# AAA-SeSi_-SCH.net
KiCad netlist of a schematic drawn in EasyEDA
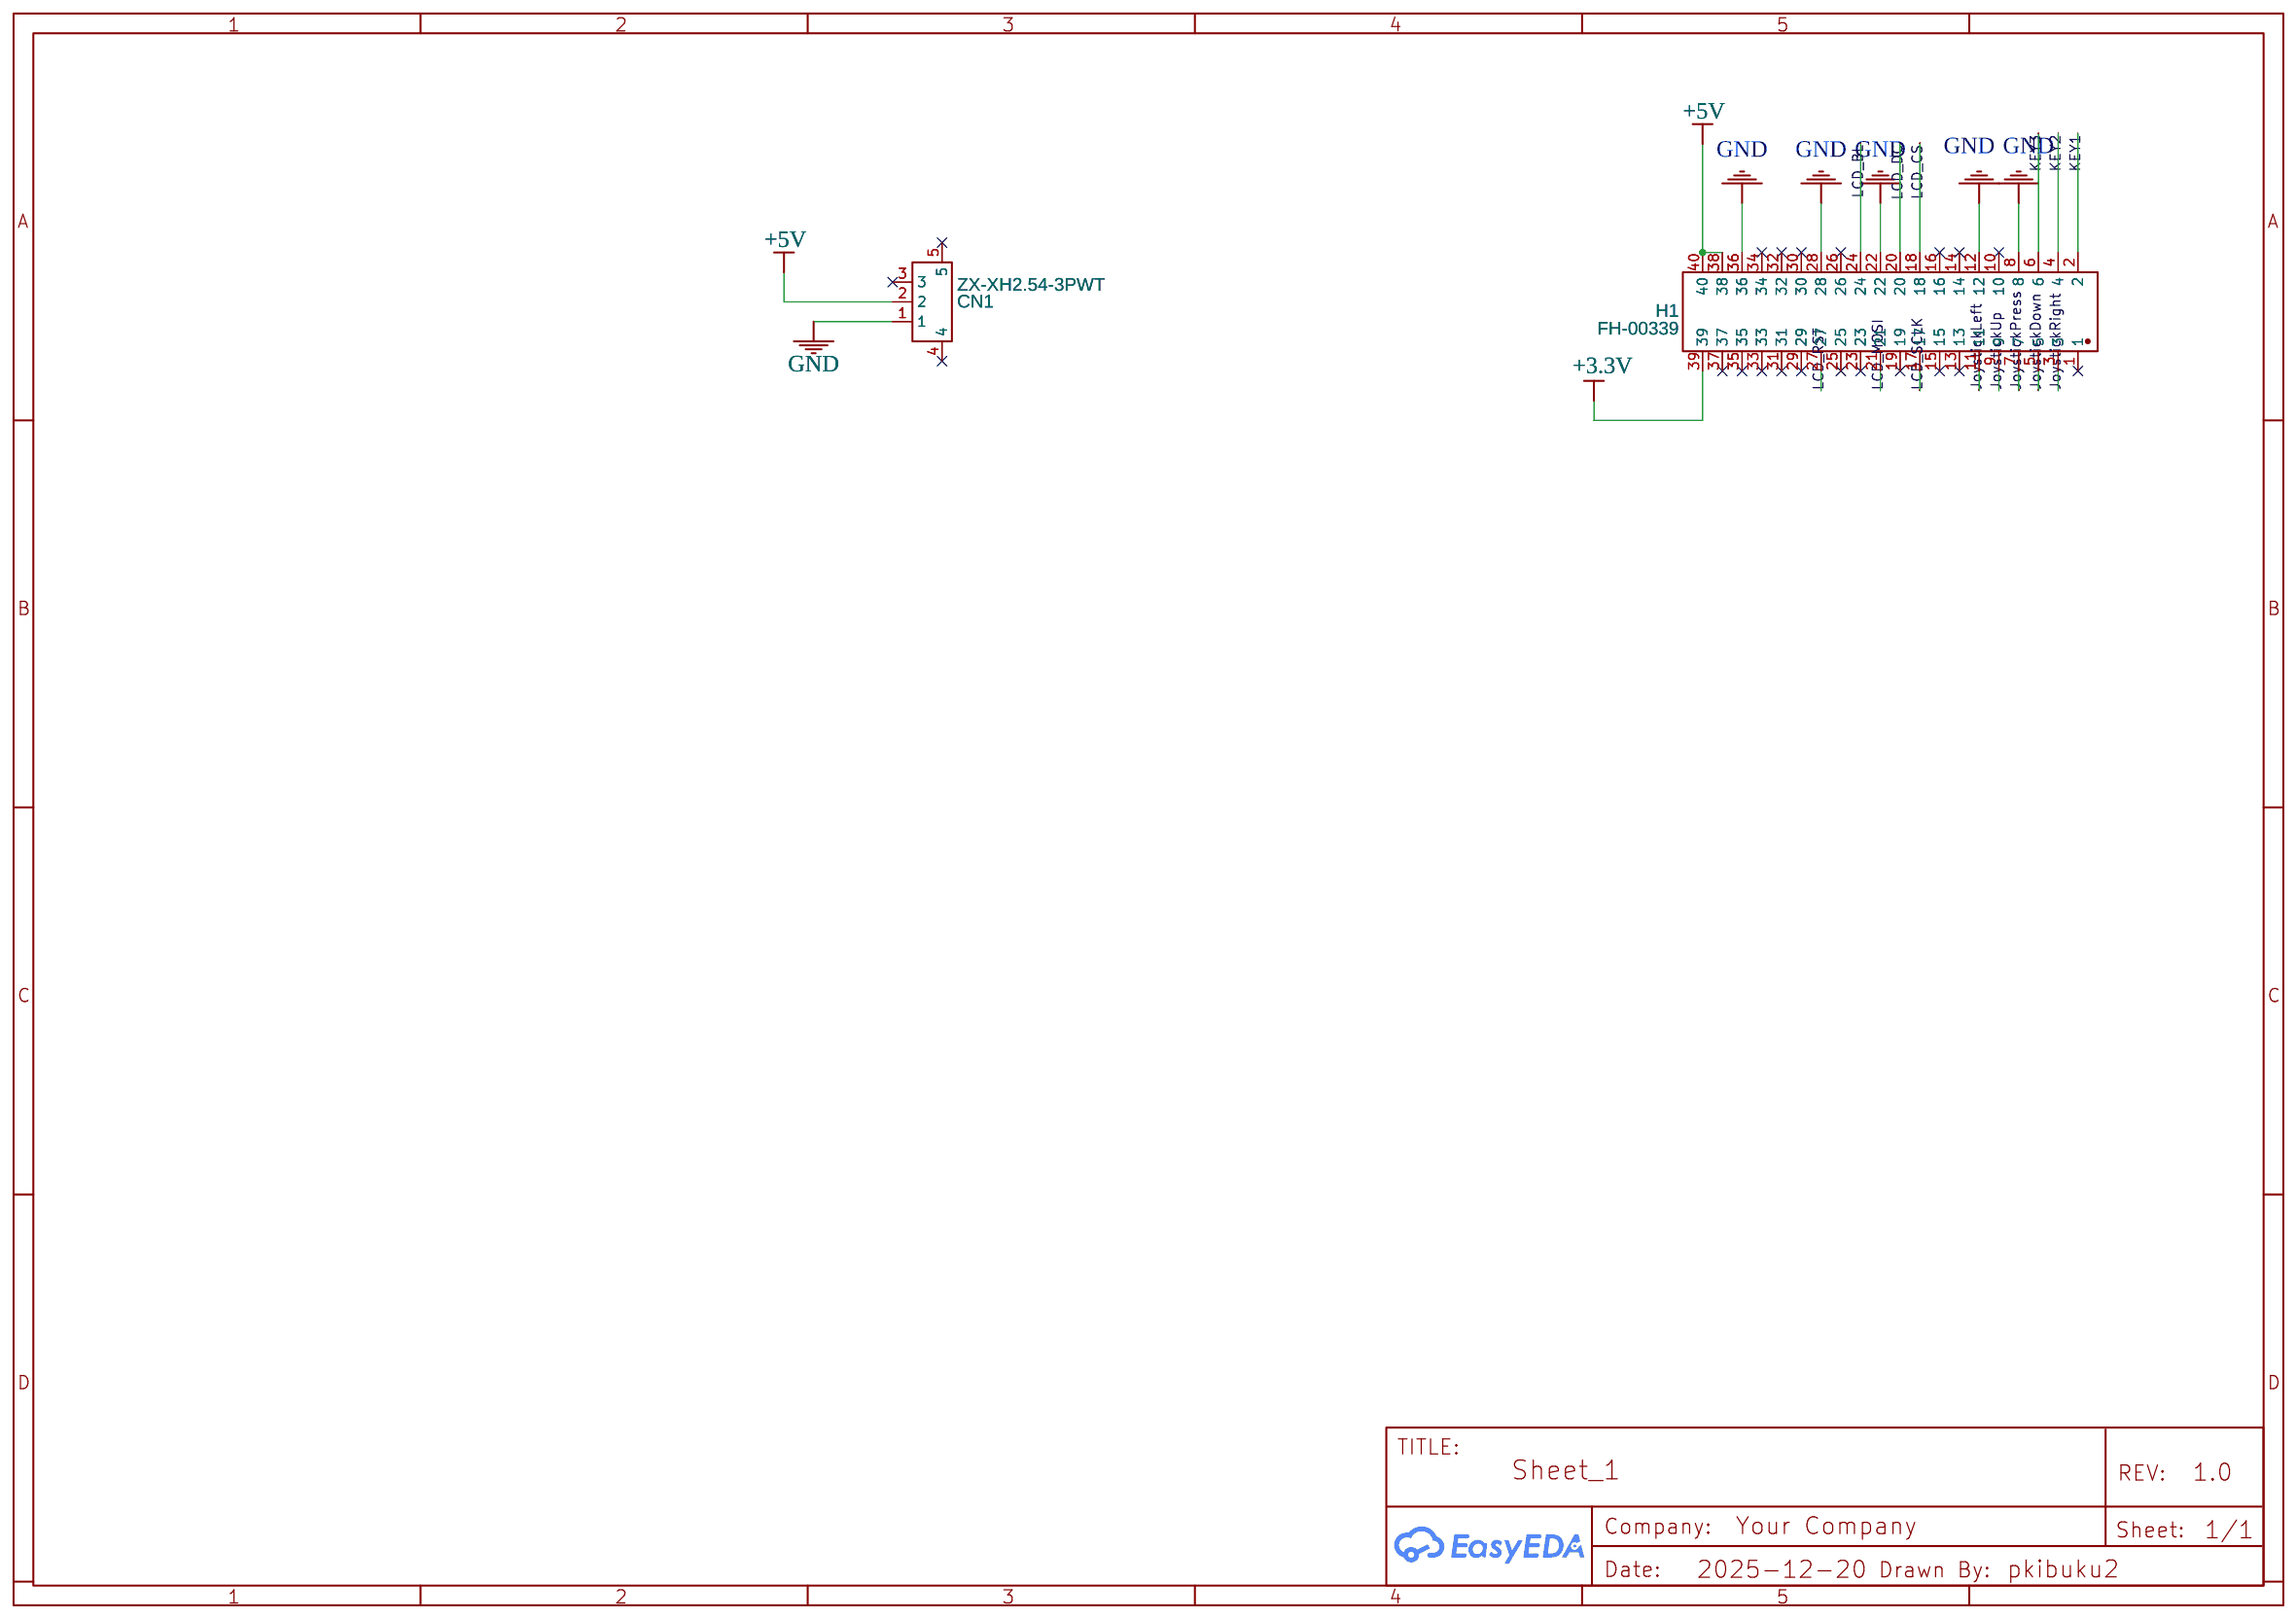
[diagram p0: Sheet_1]
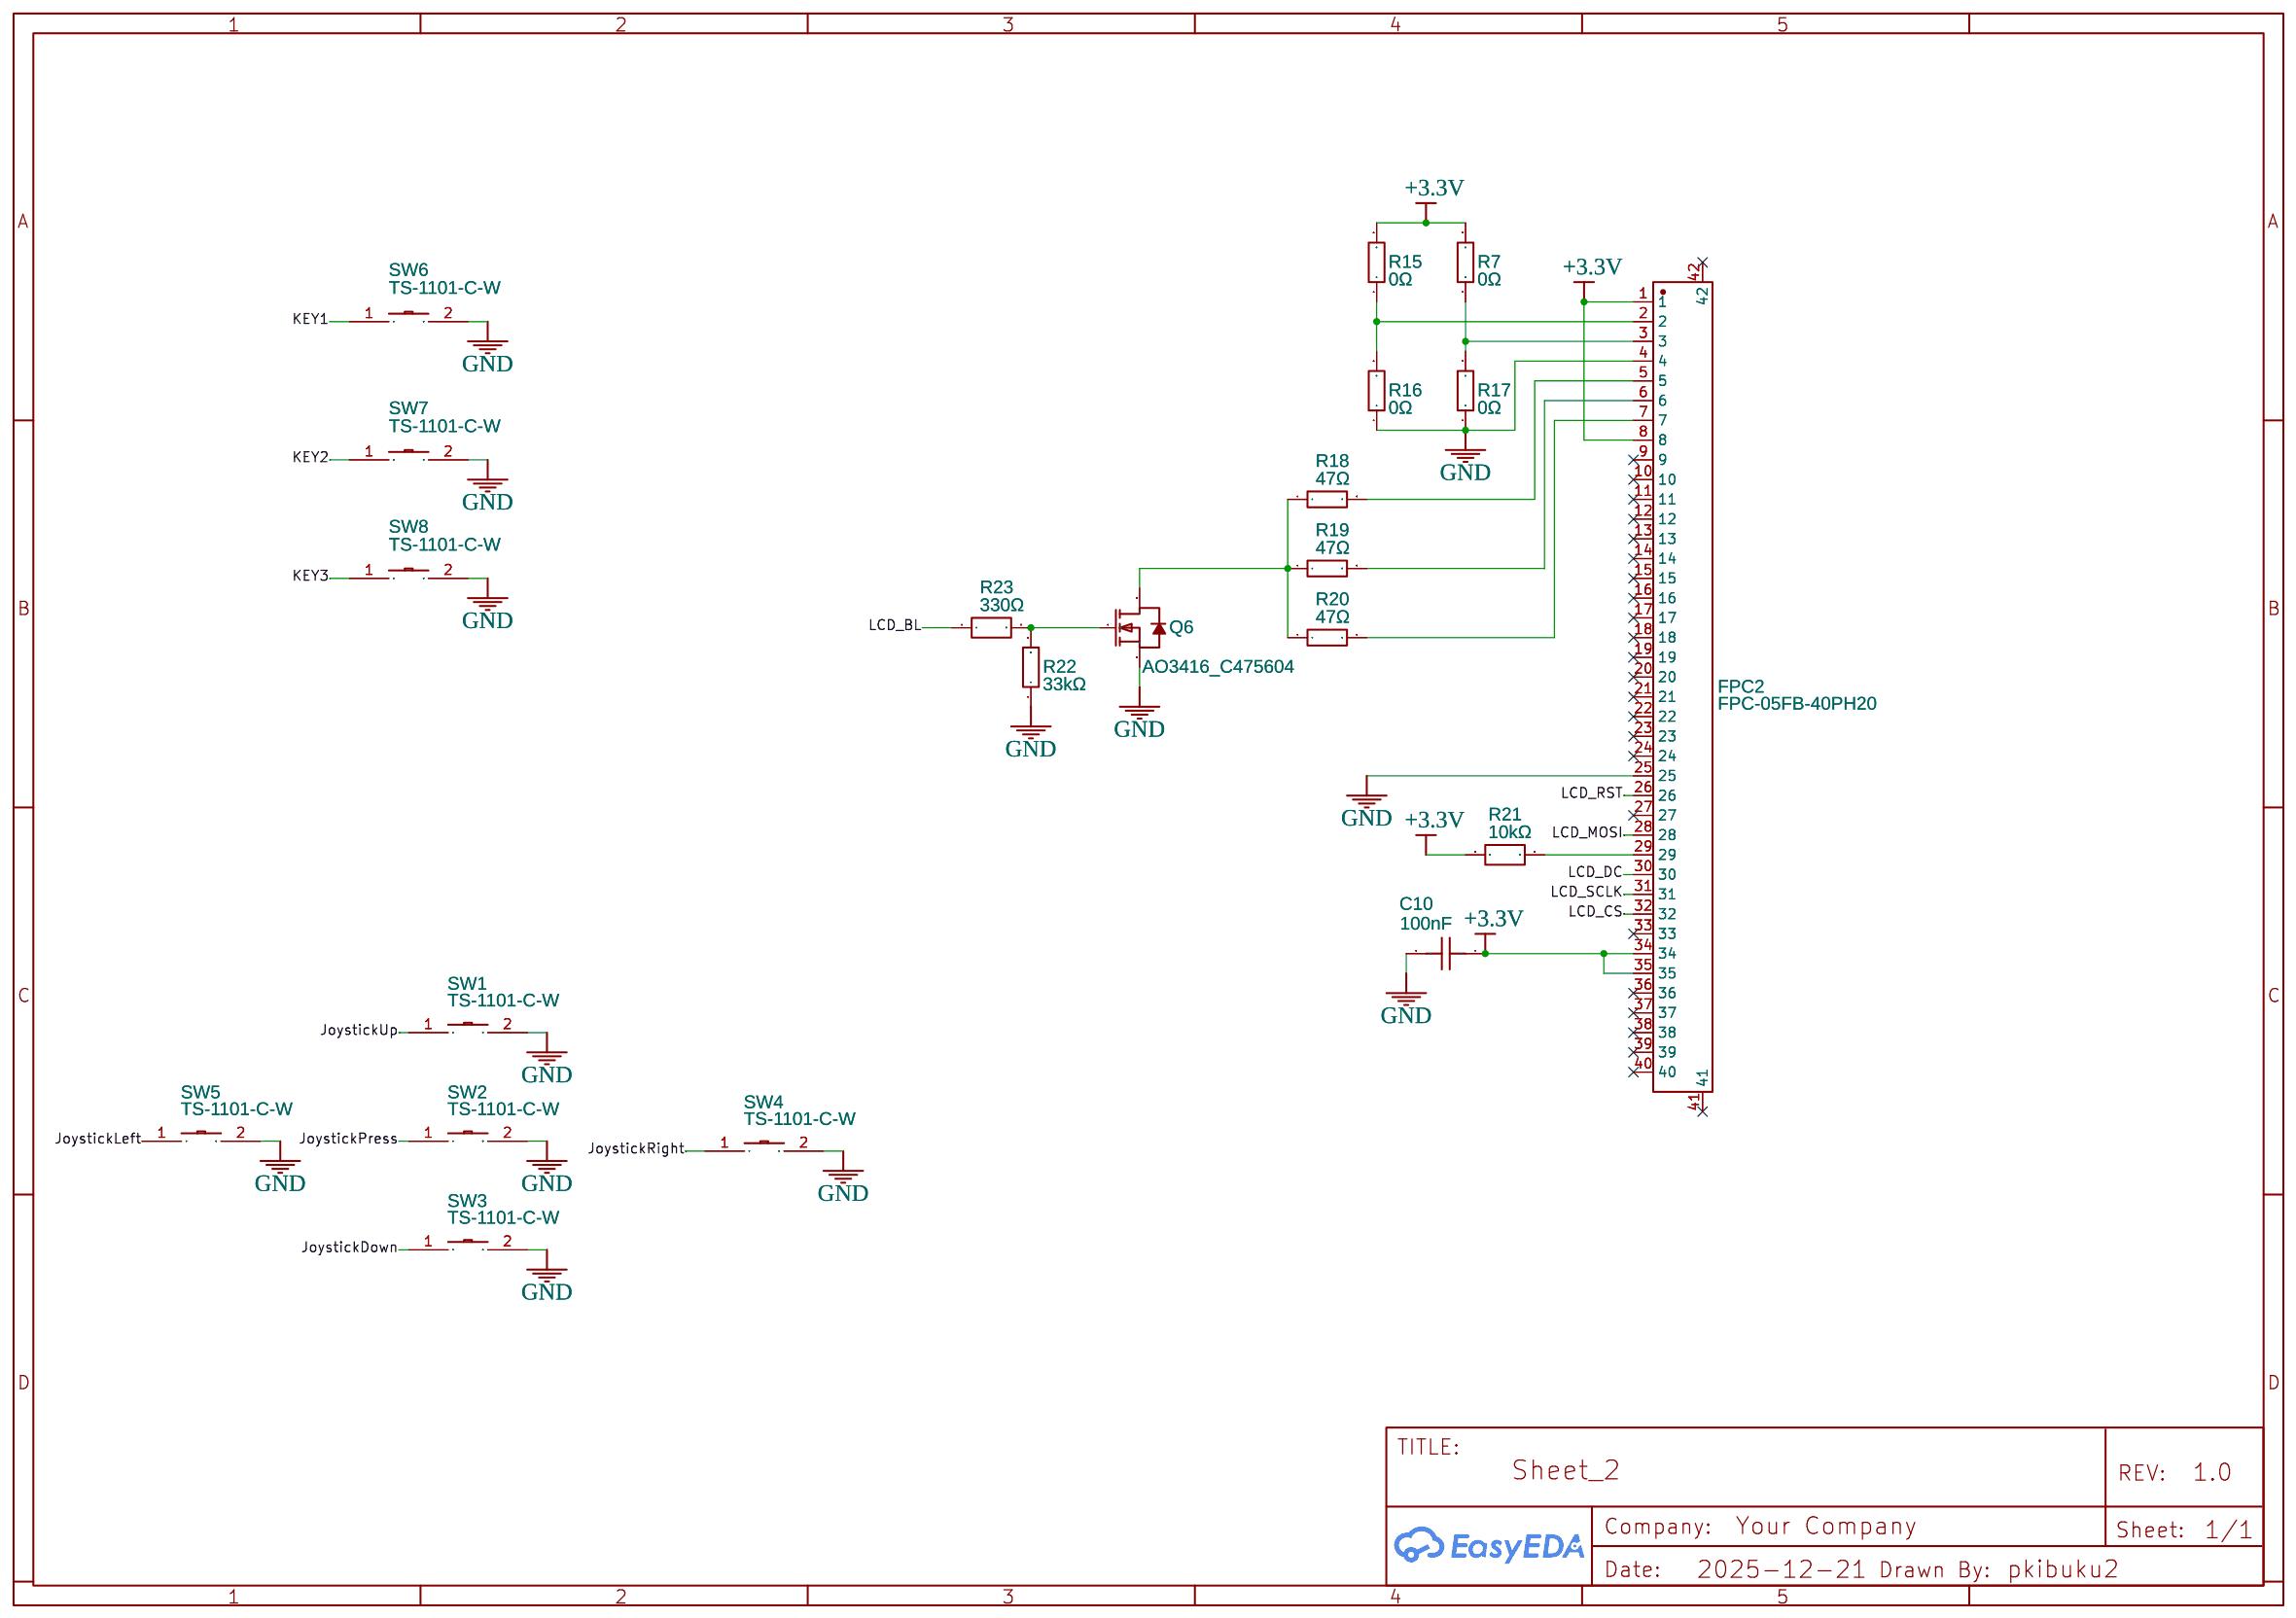
[diagram p1: Sheet_2]

(export (version "E")
  (design (tool "Eeschema 10.0.6"))
  (components
    (comp (ref "CN1")
      (value "ZX-XH2.54-3PWT")
      (fields (field (name "Manufacturer") "Megastar(兆星)"))
      (libsource (lib "") (part "ZX-XH2.54-3PWT"))
    )
    (comp (ref "H1")
      (value "FH-00339")
      (fields (field (name "Manufacturer") "Liansheng(连盛)"))
      (libsource (lib "") (part "FH-00339"))
    )
    (comp (ref "C10")
      (value "100nF")
      (fields (field (name "Manufacturer Part") "04025C104KAT2A") (field (name "Manufacturer") "Kyocera AVX"))
      (libsource (lib "") (part "04025C104KAT2A"))
    )
    (comp (ref "FPC2")
      (value "FPC-05FB-40PH20")
      (fields (field (name "Manufacturer") "XUNPU(讯普)"))
      (libsource (lib "") (part "FPC-05FB-40PH20"))
    )
    (comp (ref "Q6")
      (value "AO3416_C475604")
      (fields (field (name "Manufacturer Part") "SK3416") (field (name "Manufacturer") "SHIKUES(时科)"))
      (libsource (lib "") (part "AO3416_C475604"))
    )
    (comp (ref "R7")
      (value "0Ω")
      (fields
        (field (name "Manufacturer Part") "0402WGF0000TCE")
        (field (name "Manufacturer") "UNI-ROYAL(厚声)")
      )
      (libsource (lib "") (part "0402WGF0000TCE"))
    )
    (comp (ref "R15")
      (value "0Ω")
      (fields
        (field (name "Manufacturer Part") "0402WGF0000TCE")
        (field (name "Manufacturer") "UNI-ROYAL(厚声)")
      )
      (libsource (lib "") (part "0402WGF0000TCE"))
    )
    (comp (ref "R16")
      (value "0Ω")
      (fields
        (field (name "Manufacturer Part") "0402WGF0000TCE")
        (field (name "Manufacturer") "UNI-ROYAL(厚声)")
      )
      (libsource (lib "") (part "0402WGF0000TCE"))
    )
    (comp (ref "R17")
      (value "0Ω")
      (fields
        (field (name "Manufacturer Part") "0402WGF0000TCE")
        (field (name "Manufacturer") "UNI-ROYAL(厚声)")
      )
      (libsource (lib "") (part "0402WGF0000TCE"))
    )
    (comp (ref "R18")
      (value "47Ω")
      (fields
        (field (name "Manufacturer Part") "0402WGJ0470TCE")
        (field (name "Manufacturer") "UNI-ROYAL(厚声)")
      )
      (libsource (lib "") (part "0402WGJ0470TCE"))
    )
    (comp (ref "R19")
      (value "47Ω")
      (fields
        (field (name "Manufacturer Part") "0402WGJ0470TCE")
        (field (name "Manufacturer") "UNI-ROYAL(厚声)")
      )
      (libsource (lib "") (part "0402WGJ0470TCE"))
    )
    (comp (ref "R20")
      (value "47Ω")
      (fields
        (field (name "Manufacturer Part") "0402WGJ0470TCE")
        (field (name "Manufacturer") "UNI-ROYAL(厚声)")
      )
      (libsource (lib "") (part "0402WGJ0470TCE"))
    )
    (comp (ref "R21")
      (value "10kΩ")
      (fields
        (field (name "Manufacturer Part") "0402WGD1002TCE")
        (field (name "Manufacturer") "UNI-ROYAL(厚声)")
      )
      (libsource (lib "") (part "0402WGD1002TCE"))
    )
    (comp (ref "R22")
      (value "33kΩ")
      (fields
        (field (name "Manufacturer Part") "0402WGF3302TCE")
        (field (name "Manufacturer") "UNI-ROYAL(厚声)")
      )
      (libsource (lib "") (part "0402WGF3302TCE"))
    )
    (comp (ref "R23")
      (value "330Ω")
      (fields
        (field (name "Manufacturer Part") "0402WGD3300TCE")
        (field (name "Manufacturer") "UNI-ROYAL(厚声)")
      )
      (libsource (lib "") (part "0402WGD3300TCE"))
    )
    (comp (ref "SW1")
      (value "TS-1101-C-W")
      (fields (field (name "Manufacturer") "XKB Connectivity(中国星坤)"))
      (libsource (lib "") (part "TS-1101-C-W"))
    )
    (comp (ref "SW2")
      (value "TS-1101-C-W")
      (fields (field (name "Manufacturer") "XKB Connectivity(中国星坤)"))
      (libsource (lib "") (part "TS-1101-C-W"))
    )
    (comp (ref "SW3")
      (value "TS-1101-C-W")
      (fields (field (name "Manufacturer") "XKB Connectivity(中国星坤)"))
      (libsource (lib "") (part "TS-1101-C-W"))
    )
    (comp (ref "SW4")
      (value "TS-1101-C-W")
      (fields (field (name "Manufacturer") "XKB Connectivity(中国星坤)"))
      (libsource (lib "") (part "TS-1101-C-W"))
    )
    (comp (ref "SW5")
      (value "TS-1101-C-W")
      (fields (field (name "Manufacturer") "XKB Connectivity(中国星坤)"))
      (libsource (lib "") (part "TS-1101-C-W"))
    )
    (comp (ref "SW6")
      (value "TS-1101-C-W")
      (fields (field (name "Manufacturer") "XKB Connectivity(中国星坤)"))
      (libsource (lib "") (part "TS-1101-C-W"))
    )
    (comp (ref "SW7")
      (value "TS-1101-C-W")
      (fields (field (name "Manufacturer") "XKB Connectivity(中国星坤)"))
      (libsource (lib "") (part "TS-1101-C-W"))
    )
    (comp (ref "SW8")
      (value "TS-1101-C-W")
      (fields (field (name "Manufacturer") "XKB Connectivity(中国星坤)"))
      (libsource (lib "") (part "TS-1101-C-W"))
    )
  )
  (nets
    (net (code "1") (name "+3.3V") (class "Default")
      (node (ref "C10") (pin "1") (pinfunction "1_1") (pintype "unspecified"))
      (node (ref "FPC2") (pin "1") (pinfunction "1_1") (pintype "unspecified"))
      (node (ref "FPC2") (pin "34") (pinfunction "34_34") (pintype "unspecified"))
      (node (ref "FPC2") (pin "35") (pinfunction "35_35") (pintype "unspecified"))
      (node (ref "FPC2") (pin "8") (pinfunction "8_8") (pintype "unspecified"))
      (node (ref "H1") (pin "39") (pinfunction "39_39") (pintype "unspecified"))
      (node (ref "R15") (pin "2") (pinfunction "2_2") (pintype "input"))
      (node (ref "R21") (pin "2") (pinfunction "2_2") (pintype "unspecified"))
      (node (ref "R7") (pin "2") (pinfunction "2_2") (pintype "input"))
    )
    (net (code "2") (name "+5V") (class "Default")
      (node (ref "CN1") (pin "2") (pinfunction "2_2") (pintype "unspecified"))
      (node (ref "H1") (pin "38") (pinfunction "38_38") (pintype "unspecified"))
      (node (ref "H1") (pin "40") (pinfunction "40_40") (pintype "unspecified"))
    )
    (net (code "3") (name "GND") (class "Default")
      (node (ref "C10") (pin "2") (pinfunction "2_2") (pintype "unspecified"))
      (node (ref "CN1") (pin "1") (pinfunction "1_1") (pintype "unspecified"))
      (node (ref "FPC2") (pin "25") (pinfunction "25_25") (pintype "unspecified"))
      (node (ref "FPC2") (pin "4") (pinfunction "4_4") (pintype "unspecified"))
      (node (ref "H1") (pin "12") (pinfunction "12_12") (pintype "unspecified"))
      (node (ref "H1") (pin "22") (pinfunction "22_22") (pintype "unspecified"))
      (node (ref "H1") (pin "28") (pinfunction "28_28") (pintype "unspecified"))
      (node (ref "H1") (pin "36") (pinfunction "36_36") (pintype "unspecified"))
      (node (ref "H1") (pin "8") (pinfunction "8_8") (pintype "unspecified"))
      (node (ref "Q6") (pin "2") (pinfunction "S_2") (pintype "unspecified"))
      (node (ref "R16") (pin "1") (pinfunction "1_1") (pintype "input"))
      (node (ref "R17") (pin "1") (pinfunction "1_1") (pintype "input"))
      (node (ref "R22") (pin "1") (pinfunction "1_1") (pintype "input"))
      (node (ref "SW1") (pin "2") (pinfunction "2_2") (pintype "unspecified"))
      (node (ref "SW2") (pin "2") (pinfunction "2_2") (pintype "unspecified"))
      (node (ref "SW3") (pin "2") (pinfunction "2_2") (pintype "unspecified"))
      (node (ref "SW4") (pin "2") (pinfunction "2_2") (pintype "unspecified"))
      (node (ref "SW5") (pin "2") (pinfunction "2_2") (pintype "unspecified"))
      (node (ref "SW6") (pin "2") (pinfunction "2_2") (pintype "unspecified"))
      (node (ref "SW7") (pin "2") (pinfunction "2_2") (pintype "unspecified"))
      (node (ref "SW8") (pin "2") (pinfunction "2_2") (pintype "unspecified"))
    )
    (net (code "4") (name "JoystickDown") (class "Default")
      (node (ref "H1") (pin "5") (pinfunction "5_5") (pintype "unspecified"))
      (node (ref "SW3") (pin "1") (pinfunction "1_1") (pintype "unspecified"))
    )
    (net (code "5") (name "JoystickLeft") (class "Default")
      (node (ref "H1") (pin "11") (pinfunction "11_11") (pintype "unspecified"))
      (node (ref "SW5") (pin "1") (pinfunction "1_1") (pintype "unspecified"))
    )
    (net (code "6") (name "JoystickPress") (class "Default")
      (node (ref "H1") (pin "7") (pinfunction "7_7") (pintype "unspecified"))
      (node (ref "SW2") (pin "1") (pinfunction "1_1") (pintype "unspecified"))
    )
    (net (code "7") (name "JoystickRight") (class "Default")
      (node (ref "H1") (pin "3") (pinfunction "3_3") (pintype "unspecified"))
      (node (ref "SW4") (pin "1") (pinfunction "1_1") (pintype "unspecified"))
    )
    (net (code "8") (name "JoystickUp") (class "Default")
      (node (ref "H1") (pin "9") (pinfunction "9_9") (pintype "unspecified"))
      (node (ref "SW1") (pin "1") (pinfunction "1_1") (pintype "unspecified"))
    )
    (net (code "9") (name "KEY1") (class "Default")
      (node (ref "H1") (pin "2") (pinfunction "2_2") (pintype "unspecified"))
      (node (ref "SW6") (pin "1") (pinfunction "1_1") (pintype "unspecified"))
    )
    (net (code "10") (name "KEY2") (class "Default")
      (node (ref "H1") (pin "4") (pinfunction "4_4") (pintype "unspecified"))
      (node (ref "SW7") (pin "1") (pinfunction "1_1") (pintype "unspecified"))
    )
    (net (code "11") (name "KEY3") (class "Default")
      (node (ref "H1") (pin "6") (pinfunction "6_6") (pintype "unspecified"))
      (node (ref "SW8") (pin "1") (pinfunction "1_1") (pintype "unspecified"))
    )
    (net (code "12") (name "LCD_BL") (class "Default")
      (node (ref "H1") (pin "24") (pinfunction "24_24") (pintype "unspecified"))
      (node (ref "R23") (pin "1") (pinfunction "1_1") (pintype "unspecified"))
    )
    (net (code "13") (name "LCD_CS") (class "Default")
      (node (ref "FPC2") (pin "32") (pinfunction "32_32") (pintype "unspecified"))
      (node (ref "H1") (pin "18") (pinfunction "18_18") (pintype "unspecified"))
    )
    (net (code "14") (name "LCD_DC") (class "Default")
      (node (ref "FPC2") (pin "30") (pinfunction "30_30") (pintype "unspecified"))
      (node (ref "H1") (pin "20") (pinfunction "20_20") (pintype "unspecified"))
    )
    (net (code "15") (name "LCD_MOSI") (class "Default")
      (node (ref "FPC2") (pin "28") (pinfunction "28_28") (pintype "unspecified"))
      (node (ref "H1") (pin "21") (pinfunction "21_21") (pintype "unspecified"))
    )
    (net (code "16") (name "LCD_RST") (class "Default")
      (node (ref "FPC2") (pin "26") (pinfunction "26_26") (pintype "unspecified"))
      (node (ref "H1") (pin "27") (pinfunction "27_27") (pintype "unspecified"))
    )
    (net (code "17") (name "LCD_SCLK") (class "Default")
      (node (ref "FPC2") (pin "31") (pinfunction "31_31") (pintype "unspecified"))
      (node (ref "H1") (pin "17") (pinfunction "17_17") (pintype "unspecified"))
    )
    (net (code "18") (name "Net-(FPC2-Pad2)") (class "Default")
      (node (ref "FPC2") (pin "2") (pinfunction "2_2") (pintype "unspecified"))
      (node (ref "R15") (pin "1") (pinfunction "1_1") (pintype "input"))
      (node (ref "R16") (pin "2") (pinfunction "2_2") (pintype "input"))
    )
    (net (code "19") (name "Net-(FPC2-Pad3)") (class "Default")
      (node (ref "FPC2") (pin "3") (pinfunction "3_3") (pintype "unspecified"))
      (node (ref "R17") (pin "2") (pinfunction "2_2") (pintype "input"))
      (node (ref "R7") (pin "1") (pinfunction "1_1") (pintype "input"))
    )
    (net (code "20") (name "Net-(FPC2-Pad5)") (class "Default")
      (node (ref "FPC2") (pin "5") (pinfunction "5_5") (pintype "unspecified"))
      (node (ref "R18") (pin "2") (pinfunction "2_2") (pintype "input"))
    )
    (net (code "21") (name "Net-(FPC2-Pad6)") (class "Default")
      (node (ref "FPC2") (pin "6") (pinfunction "6_6") (pintype "unspecified"))
      (node (ref "R19") (pin "2") (pinfunction "2_2") (pintype "input"))
    )
    (net (code "22") (name "Net-(FPC2-Pad7)") (class "Default")
      (node (ref "FPC2") (pin "7") (pinfunction "7_7") (pintype "unspecified"))
      (node (ref "R20") (pin "2") (pinfunction "2_2") (pintype "input"))
    )
    (net (code "23") (name "Net-(FPC2-Pad29)") (class "Default")
      (node (ref "FPC2") (pin "29") (pinfunction "29_29") (pintype "unspecified"))
      (node (ref "R21") (pin "1") (pinfunction "1_1") (pintype "unspecified"))
    )
    (net (code "24") (name "Net-(Q6-D)") (class "Default")
      (node (ref "Q6") (pin "3") (pinfunction "D_3") (pintype "unspecified"))
      (node (ref "R18") (pin "1") (pinfunction "1_1") (pintype "input"))
      (node (ref "R19") (pin "1") (pinfunction "1_1") (pintype "input"))
      (node (ref "R20") (pin "1") (pinfunction "1_1") (pintype "input"))
    )
    (net (code "25") (name "Net-(Q6-G)") (class "Default")
      (node (ref "Q6") (pin "1") (pinfunction "G_1") (pintype "unspecified"))
      (node (ref "R22") (pin "2") (pinfunction "2_2") (pintype "input"))
      (node (ref "R23") (pin "2") (pinfunction "2_2") (pintype "unspecified"))
    )
    (net (code "26") (name "unconnected-(CN1-Pad3)") (class "Default")
      (node (ref "CN1") (pin "3") (pinfunction "3_3") (pintype "unspecified+no_connect"))
    )
    (net (code "27") (name "unconnected-(CN1-Pad4)") (class "Default")
      (node (ref "CN1") (pin "4") (pinfunction "4_4") (pintype "unspecified+no_connect"))
    )
    (net (code "28") (name "unconnected-(CN1-Pad5)") (class "Default")
      (node (ref "CN1") (pin "5") (pinfunction "5_5") (pintype "unspecified+no_connect"))
    )
    (net (code "29") (name "unconnected-(FPC2-Pad9)") (class "Default")
      (node (ref "FPC2") (pin "9") (pinfunction "9_9") (pintype "unspecified+no_connect"))
    )
    (net (code "30") (name "unconnected-(FPC2-Pad10)") (class "Default")
      (node (ref "FPC2") (pin "10") (pinfunction "10_10") (pintype "unspecified+no_connect"))
    )
    (net (code "31") (name "unconnected-(FPC2-Pad11)") (class "Default")
      (node (ref "FPC2") (pin "11") (pinfunction "11_11") (pintype "unspecified+no_connect"))
    )
    (net (code "32") (name "unconnected-(FPC2-Pad12)") (class "Default")
      (node (ref "FPC2") (pin "12") (pinfunction "12_12") (pintype "unspecified+no_connect"))
    )
    (net (code "33") (name "unconnected-(FPC2-Pad13)") (class "Default")
      (node (ref "FPC2") (pin "13") (pinfunction "13_13") (pintype "unspecified+no_connect"))
    )
    (net (code "34") (name "unconnected-(FPC2-Pad14)") (class "Default")
      (node (ref "FPC2") (pin "14") (pinfunction "14_14") (pintype "unspecified+no_connect"))
    )
    (net (code "35") (name "unconnected-(FPC2-Pad15)") (class "Default")
      (node (ref "FPC2") (pin "15") (pinfunction "15_15") (pintype "unspecified+no_connect"))
    )
    (net (code "36") (name "unconnected-(FPC2-Pad16)") (class "Default")
      (node (ref "FPC2") (pin "16") (pinfunction "16_16") (pintype "unspecified+no_connect"))
    )
    (net (code "37") (name "unconnected-(FPC2-Pad17)") (class "Default")
      (node (ref "FPC2") (pin "17") (pinfunction "17_17") (pintype "unspecified+no_connect"))
    )
    (net (code "38") (name "unconnected-(FPC2-Pad18)") (class "Default")
      (node (ref "FPC2") (pin "18") (pinfunction "18_18") (pintype "unspecified+no_connect"))
    )
    (net (code "39") (name "unconnected-(FPC2-Pad19)") (class "Default")
      (node (ref "FPC2") (pin "19") (pinfunction "19_19") (pintype "unspecified+no_connect"))
    )
    (net (code "40") (name "unconnected-(FPC2-Pad20)") (class "Default")
      (node (ref "FPC2") (pin "20") (pinfunction "20_20") (pintype "unspecified+no_connect"))
    )
    (net (code "41") (name "unconnected-(FPC2-Pad21)") (class "Default")
      (node (ref "FPC2") (pin "21") (pinfunction "21_21") (pintype "unspecified+no_connect"))
    )
    (net (code "42") (name "unconnected-(FPC2-Pad22)") (class "Default")
      (node (ref "FPC2") (pin "22") (pinfunction "22_22") (pintype "unspecified+no_connect"))
    )
    (net (code "43") (name "unconnected-(FPC2-Pad23)") (class "Default")
      (node (ref "FPC2") (pin "23") (pinfunction "23_23") (pintype "unspecified+no_connect"))
    )
    (net (code "44") (name "unconnected-(FPC2-Pad24)") (class "Default")
      (node (ref "FPC2") (pin "24") (pinfunction "24_24") (pintype "unspecified+no_connect"))
    )
    (net (code "45") (name "unconnected-(FPC2-Pad27)") (class "Default")
      (node (ref "FPC2") (pin "27") (pinfunction "27_27") (pintype "unspecified+no_connect"))
    )
    (net (code "46") (name "unconnected-(FPC2-Pad33)") (class "Default")
      (node (ref "FPC2") (pin "33") (pinfunction "33_33") (pintype "unspecified+no_connect"))
    )
    (net (code "47") (name "unconnected-(FPC2-Pad36)") (class "Default")
      (node (ref "FPC2") (pin "36") (pinfunction "36_36") (pintype "unspecified+no_connect"))
    )
    (net (code "48") (name "unconnected-(FPC2-Pad37)") (class "Default")
      (node (ref "FPC2") (pin "37") (pinfunction "37_37") (pintype "unspecified+no_connect"))
    )
    (net (code "49") (name "unconnected-(FPC2-Pad38)") (class "Default")
      (node (ref "FPC2") (pin "38") (pinfunction "38_38") (pintype "unspecified+no_connect"))
    )
    (net (code "50") (name "unconnected-(FPC2-Pad39)") (class "Default")
      (node (ref "FPC2") (pin "39") (pinfunction "39_39") (pintype "unspecified+no_connect"))
    )
    (net (code "51") (name "unconnected-(FPC2-Pad40)") (class "Default")
      (node (ref "FPC2") (pin "40") (pinfunction "40_40") (pintype "unspecified+no_connect"))
    )
    (net (code "52") (name "unconnected-(FPC2-Pad41)") (class "Default")
      (node (ref "FPC2") (pin "41") (pinfunction "41_41") (pintype "unspecified+no_connect"))
    )
    (net (code "53") (name "unconnected-(FPC2-Pad42)") (class "Default")
      (node (ref "FPC2") (pin "42") (pinfunction "42_42") (pintype "unspecified+no_connect"))
    )
    (net (code "54") (name "unconnected-(H1-Pad1)") (class "Default")
      (node (ref "H1") (pin "1") (pinfunction "1_1") (pintype "unspecified+no_connect"))
    )
    (net (code "55") (name "unconnected-(H1-Pad10)") (class "Default")
      (node (ref "H1") (pin "10") (pinfunction "10_10") (pintype "unspecified+no_connect"))
    )
    (net (code "56") (name "unconnected-(H1-Pad13)") (class "Default")
      (node (ref "H1") (pin "13") (pinfunction "13_13") (pintype "unspecified+no_connect"))
    )
    (net (code "57") (name "unconnected-(H1-Pad14)") (class "Default")
      (node (ref "H1") (pin "14") (pinfunction "14_14") (pintype "unspecified+no_connect"))
    )
    (net (code "58") (name "unconnected-(H1-Pad15)") (class "Default")
      (node (ref "H1") (pin "15") (pinfunction "15_15") (pintype "unspecified+no_connect"))
    )
    (net (code "59") (name "unconnected-(H1-Pad16)") (class "Default")
      (node (ref "H1") (pin "16") (pinfunction "16_16") (pintype "unspecified+no_connect"))
    )
    (net (code "60") (name "unconnected-(H1-Pad19)") (class "Default")
      (node (ref "H1") (pin "19") (pinfunction "19_19") (pintype "unspecified+no_connect"))
    )
    (net (code "61") (name "unconnected-(H1-Pad23)") (class "Default")
      (node (ref "H1") (pin "23") (pinfunction "23_23") (pintype "unspecified+no_connect"))
    )
    (net (code "62") (name "unconnected-(H1-Pad25)") (class "Default")
      (node (ref "H1") (pin "25") (pinfunction "25_25") (pintype "unspecified+no_connect"))
    )
    (net (code "63") (name "unconnected-(H1-Pad26)") (class "Default")
      (node (ref "H1") (pin "26") (pinfunction "26_26") (pintype "unspecified+no_connect"))
    )
    (net (code "64") (name "unconnected-(H1-Pad29)") (class "Default")
      (node (ref "H1") (pin "29") (pinfunction "29_29") (pintype "unspecified+no_connect"))
    )
    (net (code "65") (name "unconnected-(H1-Pad30)") (class "Default")
      (node (ref "H1") (pin "30") (pinfunction "30_30") (pintype "unspecified+no_connect"))
    )
    (net (code "66") (name "unconnected-(H1-Pad31)") (class "Default")
      (node (ref "H1") (pin "31") (pinfunction "31_31") (pintype "unspecified+no_connect"))
    )
    (net (code "67") (name "unconnected-(H1-Pad32)") (class "Default")
      (node (ref "H1") (pin "32") (pinfunction "32_32") (pintype "unspecified+no_connect"))
    )
    (net (code "68") (name "unconnected-(H1-Pad33)") (class "Default")
      (node (ref "H1") (pin "33") (pinfunction "33_33") (pintype "unspecified+no_connect"))
    )
    (net (code "69") (name "unconnected-(H1-Pad34)") (class "Default")
      (node (ref "H1") (pin "34") (pinfunction "34_34") (pintype "unspecified+no_connect"))
    )
    (net (code "70") (name "unconnected-(H1-Pad35)") (class "Default")
      (node (ref "H1") (pin "35") (pinfunction "35_35") (pintype "unspecified+no_connect"))
    )
    (net (code "71") (name "unconnected-(H1-Pad37)") (class "Default")
      (node (ref "H1") (pin "37") (pinfunction "37_37") (pintype "unspecified+no_connect"))
    )
  )
)
